# AM1027_LEDS_REV01.net
KiCad netlist of a schematic drawn in EAGLE
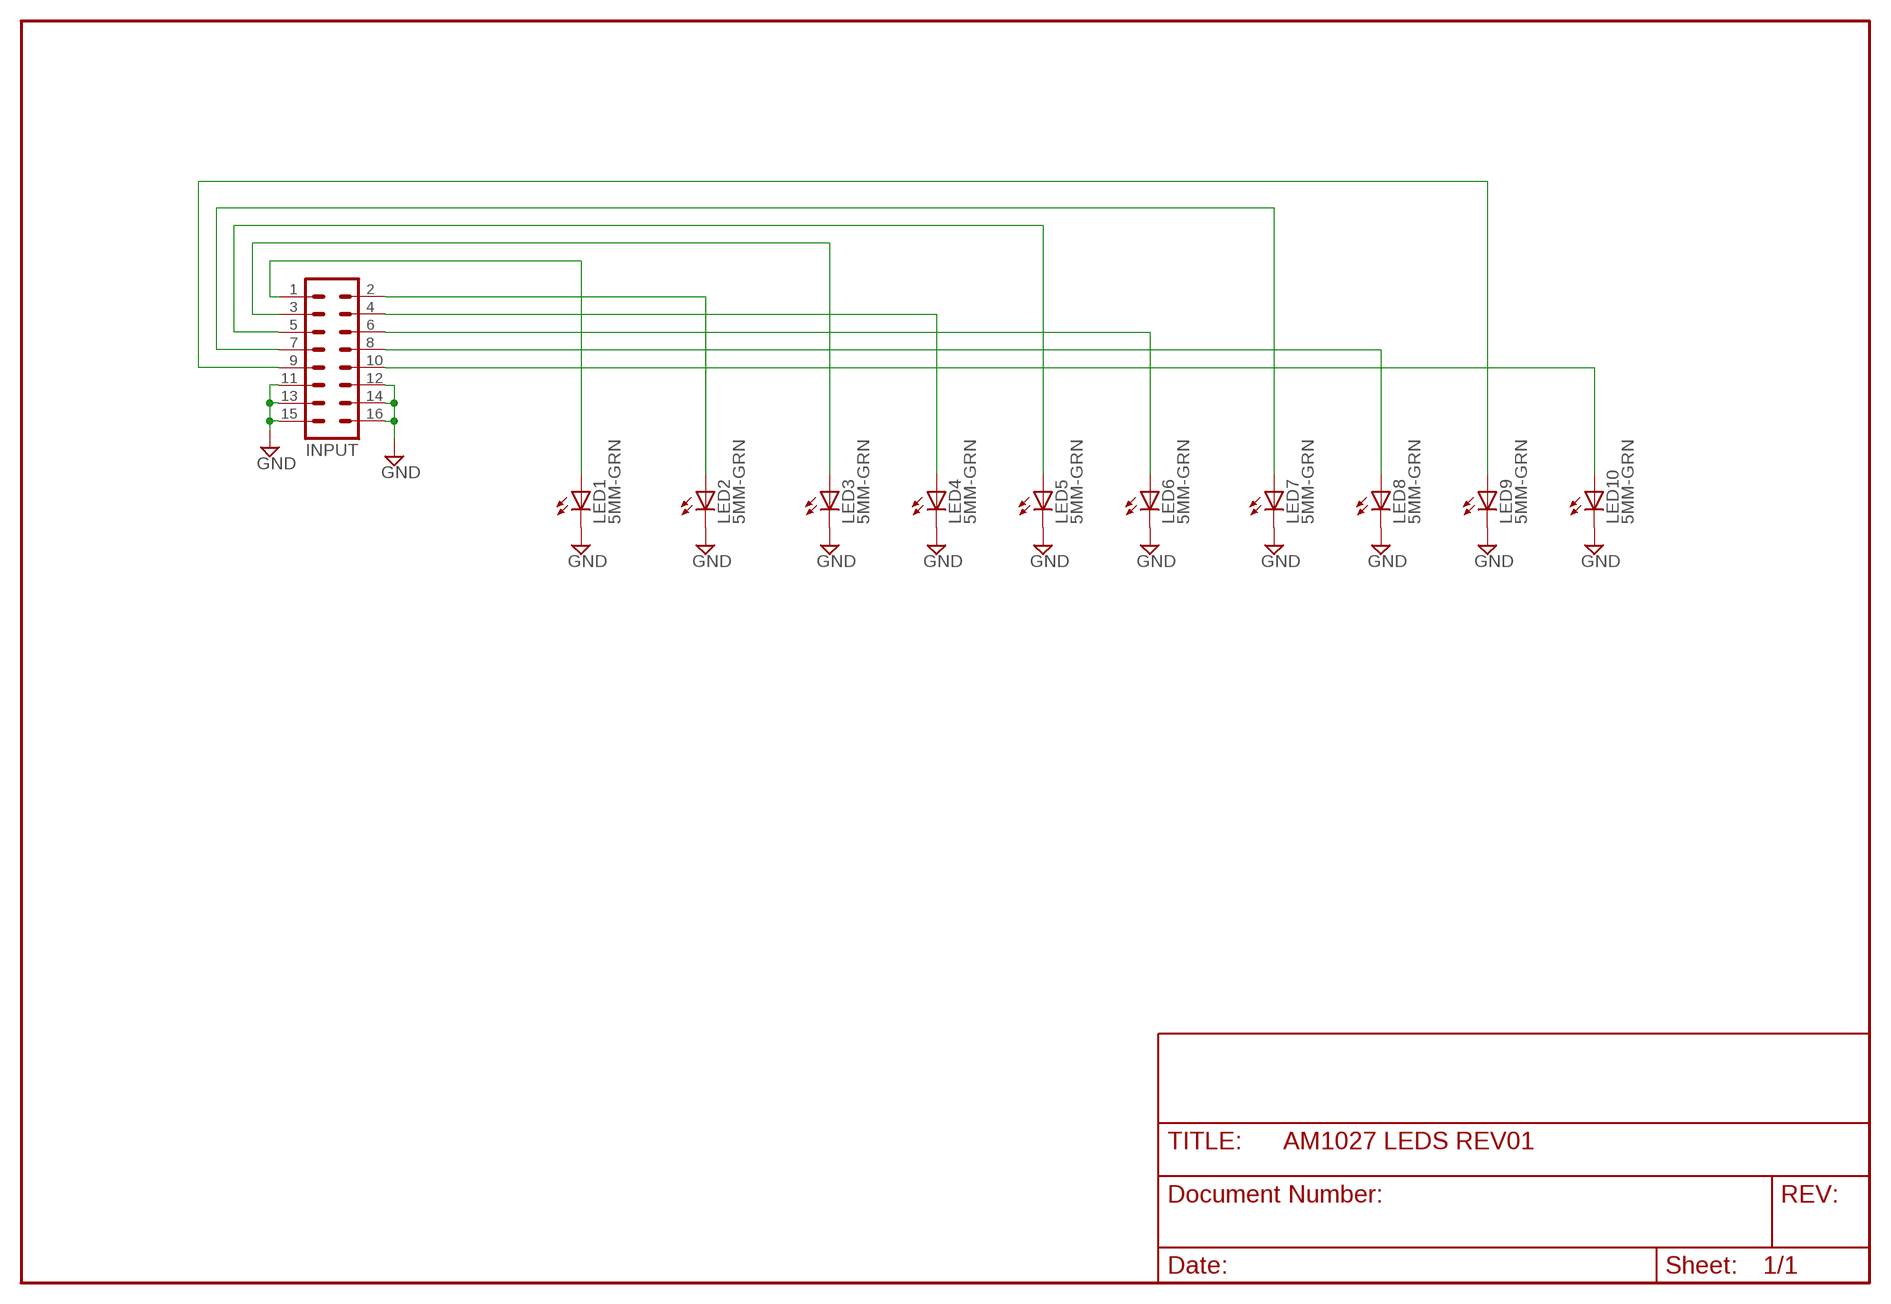
[diagram p0: schematic, sheet 1]

(export (version "E")
  (design (tool "Eeschema 10.0.6"))
  (components
    (comp (ref "INPUT")
      (value "MA08-2-AM")
      (footprint "eagle-import:MA08-2-AM")
      (libsource (lib "eagle-import") (part "MA08-2-AM"))
    )
    (comp (ref "LED1")
      (value "5MM-GRN")
      (footprint "eagle-import:LED3MM-AMS")
      (libsource (lib "eagle-import") (part "LED3MM-AM"))
    )
    (comp (ref "LED2")
      (value "5MM-GRN")
      (footprint "eagle-import:LED3MM-AMS")
      (libsource (lib "eagle-import") (part "LED3MM-AM"))
    )
    (comp (ref "LED3")
      (value "5MM-GRN")
      (footprint "eagle-import:LED3MM-AMS")
      (libsource (lib "eagle-import") (part "LED3MM-AM"))
    )
    (comp (ref "LED4")
      (value "5MM-GRN")
      (footprint "eagle-import:LED3MM-AMS")
      (libsource (lib "eagle-import") (part "LED3MM-AM"))
    )
    (comp (ref "LED5")
      (value "5MM-GRN")
      (footprint "eagle-import:LED3MM-AMS")
      (libsource (lib "eagle-import") (part "LED3MM-AM"))
    )
    (comp (ref "LED6")
      (value "5MM-GRN")
      (footprint "eagle-import:LED3MM-AMS")
      (libsource (lib "eagle-import") (part "LED3MM-AM"))
    )
    (comp (ref "LED7")
      (value "5MM-GRN")
      (footprint "eagle-import:LED3MM-AMS")
      (libsource (lib "eagle-import") (part "LED3MM-AM"))
    )
    (comp (ref "LED8")
      (value "5MM-GRN")
      (footprint "eagle-import:LED3MM-AMS")
      (libsource (lib "eagle-import") (part "LED3MM-AM"))
    )
    (comp (ref "LED9")
      (value "5MM-GRN")
      (footprint "eagle-import:LED3MM-AMS")
      (libsource (lib "eagle-import") (part "LED3MM-AM"))
    )
    (comp (ref "LED10")
      (value "5MM-GRN")
      (footprint "eagle-import:LED3MM-AMS")
      (libsource (lib "eagle-import") (part "LED3MM-AM"))
    )
  )
  (nets
    (net (code "1") (name "GND") (class "Default")
      (node (ref "INPUT") (pin "11") (pinfunction "11_11") (pintype "passive"))
      (node (ref "INPUT") (pin "12") (pinfunction "12_12") (pintype "passive"))
      (node (ref "INPUT") (pin "13") (pinfunction "13_13") (pintype "passive"))
      (node (ref "INPUT") (pin "14") (pinfunction "14_14") (pintype "passive"))
      (node (ref "INPUT") (pin "15") (pinfunction "15_15") (pintype "passive"))
      (node (ref "INPUT") (pin "16") (pinfunction "16_16") (pintype "passive"))
      (node (ref "LED1") (pin "C") (pinfunction "C_C") (pintype "passive"))
      (node (ref "LED10") (pin "C") (pinfunction "C_C") (pintype "passive"))
      (node (ref "LED2") (pin "C") (pinfunction "C_C") (pintype "passive"))
      (node (ref "LED3") (pin "C") (pinfunction "C_C") (pintype "passive"))
      (node (ref "LED4") (pin "C") (pinfunction "C_C") (pintype "passive"))
      (node (ref "LED5") (pin "C") (pinfunction "C_C") (pintype "passive"))
      (node (ref "LED6") (pin "C") (pinfunction "C_C") (pintype "passive"))
      (node (ref "LED7") (pin "C") (pinfunction "C_C") (pintype "passive"))
      (node (ref "LED8") (pin "C") (pinfunction "C_C") (pintype "passive"))
      (node (ref "LED9") (pin "C") (pinfunction "C_C") (pintype "passive"))
    )
    (net (code "2") (name "Net-(INPUT-Pad1)") (class "Default")
      (node (ref "INPUT") (pin "1") (pinfunction "1_1") (pintype "passive"))
      (node (ref "LED1") (pin "A") (pinfunction "A_A") (pintype "passive"))
    )
    (net (code "3") (name "Net-(INPUT-Pad2)") (class "Default")
      (node (ref "INPUT") (pin "2") (pinfunction "2_2") (pintype "passive"))
      (node (ref "LED2") (pin "A") (pinfunction "A_A") (pintype "passive"))
    )
    (net (code "4") (name "Net-(INPUT-Pad3)") (class "Default")
      (node (ref "INPUT") (pin "3") (pinfunction "3_3") (pintype "passive"))
      (node (ref "LED3") (pin "A") (pinfunction "A_A") (pintype "passive"))
    )
    (net (code "5") (name "Net-(INPUT-Pad4)") (class "Default")
      (node (ref "INPUT") (pin "4") (pinfunction "4_4") (pintype "passive"))
      (node (ref "LED4") (pin "A") (pinfunction "A_A") (pintype "passive"))
    )
    (net (code "6") (name "Net-(INPUT-Pad5)") (class "Default")
      (node (ref "INPUT") (pin "5") (pinfunction "5_5") (pintype "passive"))
      (node (ref "LED5") (pin "A") (pinfunction "A_A") (pintype "passive"))
    )
    (net (code "7") (name "Net-(INPUT-Pad6)") (class "Default")
      (node (ref "INPUT") (pin "6") (pinfunction "6_6") (pintype "passive"))
      (node (ref "LED6") (pin "A") (pinfunction "A_A") (pintype "passive"))
    )
    (net (code "8") (name "Net-(INPUT-Pad7)") (class "Default")
      (node (ref "INPUT") (pin "7") (pinfunction "7_7") (pintype "passive"))
      (node (ref "LED7") (pin "A") (pinfunction "A_A") (pintype "passive"))
    )
    (net (code "9") (name "Net-(INPUT-Pad8)") (class "Default")
      (node (ref "INPUT") (pin "8") (pinfunction "8_8") (pintype "passive"))
      (node (ref "LED8") (pin "A") (pinfunction "A_A") (pintype "passive"))
    )
    (net (code "10") (name "Net-(INPUT-Pad9)") (class "Default")
      (node (ref "INPUT") (pin "9") (pinfunction "9_9") (pintype "passive"))
      (node (ref "LED9") (pin "A") (pinfunction "A_A") (pintype "passive"))
    )
    (net (code "11") (name "Net-(INPUT-Pad10)") (class "Default")
      (node (ref "INPUT") (pin "10") (pinfunction "10_10") (pintype "passive"))
      (node (ref "LED10") (pin "A") (pinfunction "A_A") (pintype "passive"))
    )
  )
)
